# 555.net
KiCad netlist of a schematic drawn in Altium Designer
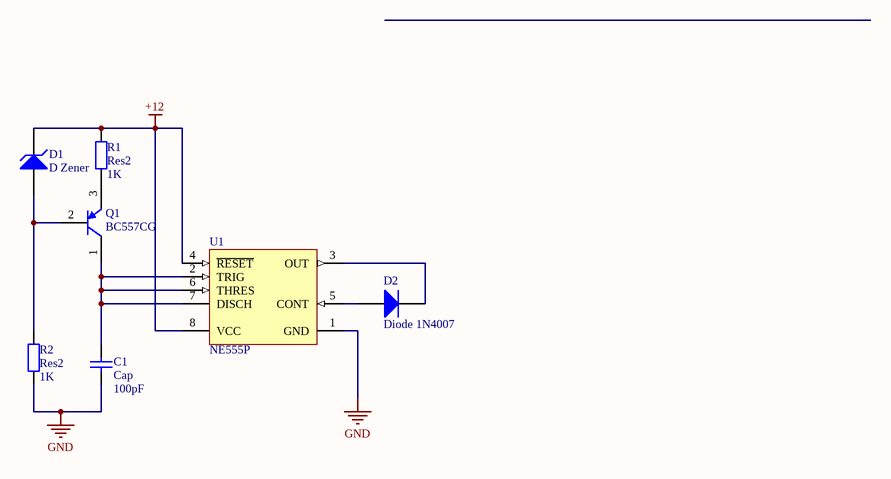
[diagram p0: 555.SchDoc]

(export (version "E")
  (design (tool "Eeschema 10.0.6"))
  (components
    (comp (ref "C1")
      (value "Cap")
      (footprint "RAD-0.3")
      (description "Capacitor")
      (fields (field (name "ALTIUM_VALUE") "100pF") (field (name "PUBLISHER") "Altium Limited"))
      (libsource (lib "Miscellaneous Devices") (part "Cap"))
    )
    (comp (ref "D1")
      (value "D Zener")
      (footprint "DIODE-0.7")
      (description "Zener Diode")
      (fields (field (name "PUBLISHER") "Altium Limited"))
      (libsource (lib "Miscellaneous Devices") (part "D Zener"))
    )
    (comp (ref "D2")
      (value "Diode 1N4007")
      (footprint "DO-41")
      (description "1 Amp General Purpose Rectifier")
      (fields (field (name "PUBLISHER") "Altium Limited"))
      (libsource (lib "Miscellaneous Devices") (part "Diode 1N4007"))
    )
    (comp (ref "Q1")
      (value "BC557CG")
      (footprint "ONSC-TO-92-3-29-11")
      (description "Amplifier Transistor, PNP Silicon, 3-Pin TO-92, Pb-Free, Bulk Box")
      (fields (field (name "MANUFACTURER") "On Semiconductor"))
      (libsource (lib "Altium Content Vault") (part "ONSC-PNP-C1B2E3-3"))
    )
    (comp (ref "R1")
      (value "Res2")
      (footprint "AXIAL-0.4")
      (description "Resistor")
      (fields (field (name "ALTIUM_VALUE") "1K") (field (name "PUBLISHER") "Altium Limited"))
      (libsource (lib "Miscellaneous Devices") (part "Res2"))
    )
    (comp (ref "R2")
      (value "Res2")
      (footprint "AXIAL-0.4")
      (description "Resistor")
      (fields (field (name "ALTIUM_VALUE") "1K") (field (name "PUBLISHER") "Altium Limited"))
      (libsource (lib "Miscellaneous Devices") (part "Res2"))
    )
    (comp (ref "U1")
      (value "NE555P")
      (footprint "P0008A")
      (description "Precision Timer, 4.5 to 16 V, 0 to 70 degC, 8-Pin DIP, Pb-Free, Tube")
      (fields (field (name "MANUFACTURER") "TexasInstruments"))
      (libsource (lib "Altium Content Vault") (part "TI-NE555-P8"))
    )
  )
  (nets
    (net (code "1") (name "+12") (class "Default")
      (node (ref "D1") (pin "2") (pinfunction "K_2") (pintype "passive"))
      (node (ref "R1") (pin "2") (pinfunction "2_2") (pintype "passive"))
      (node (ref "U1") (pin "4") (pinfunction "~{RESET}_4") (pintype "input"))
      (node (ref "U1") (pin "8") (pinfunction "VCC_8") (pintype "power_in"))
    )
    (net (code "2") (name "GND") (class "Default")
      (node (ref "C1") (pin "1") (pinfunction "1_1") (pintype "passive"))
      (node (ref "R2") (pin "1") (pinfunction "1_1") (pintype "passive"))
      (node (ref "U1") (pin "1") (pinfunction "GND_1") (pintype "power_in"))
    )
    (net (code "3") (name "Net-(D1-A)") (class "Default")
      (node (ref "D1") (pin "1") (pinfunction "A_1") (pintype "passive"))
      (node (ref "Q1") (pin "2") (pinfunction "B_2") (pintype "passive"))
      (node (ref "R2") (pin "2") (pinfunction "2_2") (pintype "passive"))
    )
    (net (code "4") (name "Net-(D2-A)") (class "Default")
      (node (ref "D2") (pin "1") (pinfunction "A_1") (pintype "passive"))
      (node (ref "U1") (pin "5") (pinfunction "CONT_5") (pintype "input"))
    )
    (net (code "5") (name "Net-(D2-K)") (class "Default")
      (node (ref "D2") (pin "2") (pinfunction "K_2") (pintype "passive"))
      (node (ref "U1") (pin "3") (pinfunction "OUT_3") (pintype "output"))
    )
    (net (code "6") (name "Net-(Q1-C)") (class "Default")
      (node (ref "C1") (pin "2") (pinfunction "2_2") (pintype "passive"))
      (node (ref "Q1") (pin "1") (pinfunction "C_1") (pintype "passive"))
      (node (ref "U1") (pin "2") (pinfunction "TRIG_2") (pintype "input"))
      (node (ref "U1") (pin "6") (pinfunction "THRES_6") (pintype "input"))
      (node (ref "U1") (pin "7") (pinfunction "DISCH_7") (pintype "open_collector"))
    )
    (net (code "7") (name "Net-(Q1-E)") (class "Default")
      (node (ref "Q1") (pin "3") (pinfunction "E_3") (pintype "passive"))
      (node (ref "R1") (pin "1") (pinfunction "1_1") (pintype "passive"))
    )
  )
)
